# BEL_PINTU_NADA.net
KiCad netlist of a schematic drawn in EAGLE
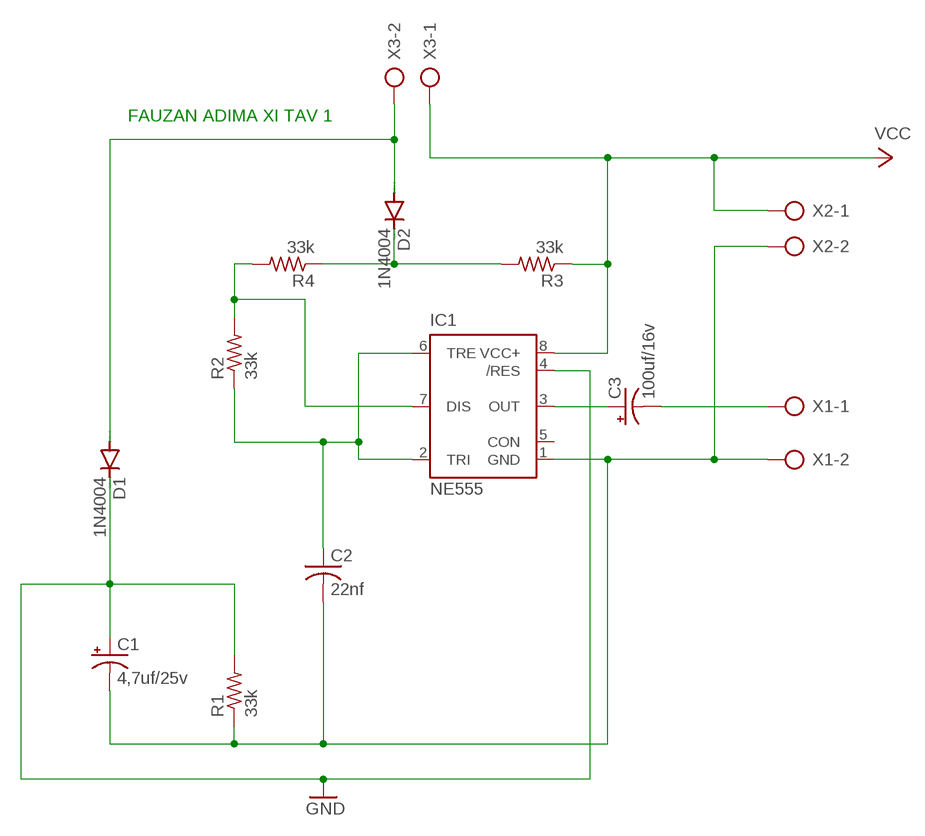
[diagram p0: schematic, sheet 1]

(export (version "E")
  (design (tool "Eeschema 10.0.6"))
  (components
    (comp (ref "C1")
      (value "4,7uf/25v")
      (footprint "eagle-import:E2-4")
      (libsource (lib "eagle-import") (part "CPOL-USE2-4"))
    )
    (comp (ref "C2")
      (value "22nf")
      (footprint "eagle-import:C025-025X050")
      (libsource (lib "eagle-import") (part "C-US025-025X050"))
    )
    (comp (ref "C3")
      (value "100uf/16v")
      (footprint "eagle-import:E2-4")
      (libsource (lib "eagle-import") (part "CPOL-USE2-4"))
    )
    (comp (ref "D1")
      (value "1N4004")
      (footprint "eagle-import:DO41-10")
      (libsource (lib "eagle-import") (part "1N4004"))
    )
    (comp (ref "D2")
      (value "1N4004")
      (footprint "eagle-import:DO41-10")
      (libsource (lib "eagle-import") (part "1N4004"))
    )
    (comp (ref "IC1")
      (value "NE555")
      (footprint "eagle-import:DIL-08")
      (fields (field (name "MF") "Arrow Electronics") (field (name "MPN") "NE555N"))
      (libsource (lib "eagle-import") (part "NE555"))
    )
    (comp (ref "R1")
      (value "33k")
      (footprint "eagle-import:0309_12")
      (libsource (lib "eagle-import") (part "R-US_0309/12"))
    )
    (comp (ref "R2")
      (value "33k")
      (footprint "eagle-import:0309_12")
      (libsource (lib "eagle-import") (part "R-US_0309/12"))
    )
    (comp (ref "R3")
      (value "33k")
      (footprint "eagle-import:0309_12")
      (libsource (lib "eagle-import") (part "R-US_0309/12"))
    )
    (comp (ref "R4")
      (value "33k")
      (footprint "eagle-import:0309_12")
      (libsource (lib "eagle-import") (part "R-US_0309/12"))
    )
    (comp (ref "X1")
      (value "AK300/2")
      (footprint "eagle-import:AK300_2")
      (libsource (lib "eagle-import") (part "AK300/2"))
    )
    (comp (ref "X2")
      (value "AK300/2")
      (footprint "eagle-import:AK300_2")
      (libsource (lib "eagle-import") (part "AK300/2"))
    )
    (comp (ref "X3")
      (value "AK300/2")
      (footprint "eagle-import:AK300_2")
      (libsource (lib "eagle-import") (part "AK300/2"))
    )
  )
  (nets
    (net (code "1") (name "GND") (class "Default")
      (node (ref "C1") (pin "+") (pinfunction "+_+") (pintype "passive"))
      (node (ref "D1") (pin "C") (pinfunction "C_C") (pintype "passive"))
      (node (ref "IC1") (pin "4") (pinfunction "/RES_4") (pintype "input"))
      (node (ref "R1") (pin "2") (pinfunction "2_2") (pintype "passive"))
    )
    (net (code "2") (name "Net-(D2-PadC)") (class "Default")
      (node (ref "D2") (pin "C") (pinfunction "C_C") (pintype "passive"))
      (node (ref "R3") (pin "2") (pinfunction "2_2") (pintype "passive"))
      (node (ref "R4") (pin "1") (pinfunction "1_1") (pintype "passive"))
    )
    (net (code "3") (name "Net-(IC1-DIS)") (class "Default")
      (node (ref "IC1") (pin "7") (pinfunction "DIS_7") (pintype "input"))
      (node (ref "R2") (pin "2") (pinfunction "2_2") (pintype "passive"))
      (node (ref "R4") (pin "2") (pinfunction "2_2") (pintype "passive"))
    )
    (net (code "4") (name "Net-(IC1-GND)") (class "Default")
      (node (ref "C1") (pin "-") (pinfunction "-_-") (pintype "passive"))
      (node (ref "C2") (pin "2") (pinfunction "2_2") (pintype "passive"))
      (node (ref "IC1") (pin "1") (pinfunction "GND_1") (pintype "power_in"))
      (node (ref "R1") (pin "1") (pinfunction "1_1") (pintype "passive"))
      (node (ref "X1") (pin "2") (pinfunction "KL_2") (pintype "passive"))
      (node (ref "X2") (pin "2") (pinfunction "KL_2") (pintype "passive"))
    )
    (net (code "5") (name "Net-(IC1-OUT)") (class "Default")
      (node (ref "C3") (pin "+") (pinfunction "+_+") (pintype "passive"))
      (node (ref "IC1") (pin "3") (pinfunction "OUT_3") (pintype "output"))
    )
    (net (code "6") (name "Net-(IC1-TRE)") (class "Default")
      (node (ref "C2") (pin "1") (pinfunction "1_1") (pintype "passive"))
      (node (ref "IC1") (pin "2") (pinfunction "TRI_2") (pintype "input"))
      (node (ref "IC1") (pin "6") (pinfunction "TRE_6") (pintype "input"))
      (node (ref "R2") (pin "1") (pinfunction "1_1") (pintype "passive"))
    )
    (net (code "7") (name "Net-(X1A-KL)") (class "Default")
      (node (ref "C3") (pin "-") (pinfunction "-_-") (pintype "passive"))
      (node (ref "X1") (pin "1") (pinfunction "KL_1") (pintype "passive"))
    )
    (net (code "8") (name "Net-(X3B-KL)") (class "Default")
      (node (ref "D1") (pin "A") (pinfunction "A_A") (pintype "passive"))
      (node (ref "D2") (pin "A") (pinfunction "A_A") (pintype "passive"))
      (node (ref "X3") (pin "2") (pinfunction "KL_2") (pintype "passive"))
    )
    (net (code "9") (name "VCC") (class "Default")
      (node (ref "IC1") (pin "8") (pinfunction "VCC+_8") (pintype "power_in"))
      (node (ref "R3") (pin "1") (pinfunction "1_1") (pintype "passive"))
      (node (ref "X2") (pin "1") (pinfunction "KL_1") (pintype "passive"))
      (node (ref "X3") (pin "1") (pinfunction "KL_1") (pintype "passive"))
    )
    (net (code "10") (name "unconnected-(IC1-CON-Pad5)") (class "Default")
      (node (ref "IC1") (pin "5") (pinfunction "CON_5") (pintype "input"))
    )
  )
)
